# 4-digit-clock.net
KiCad netlist of a schematic drawn in EAGLE
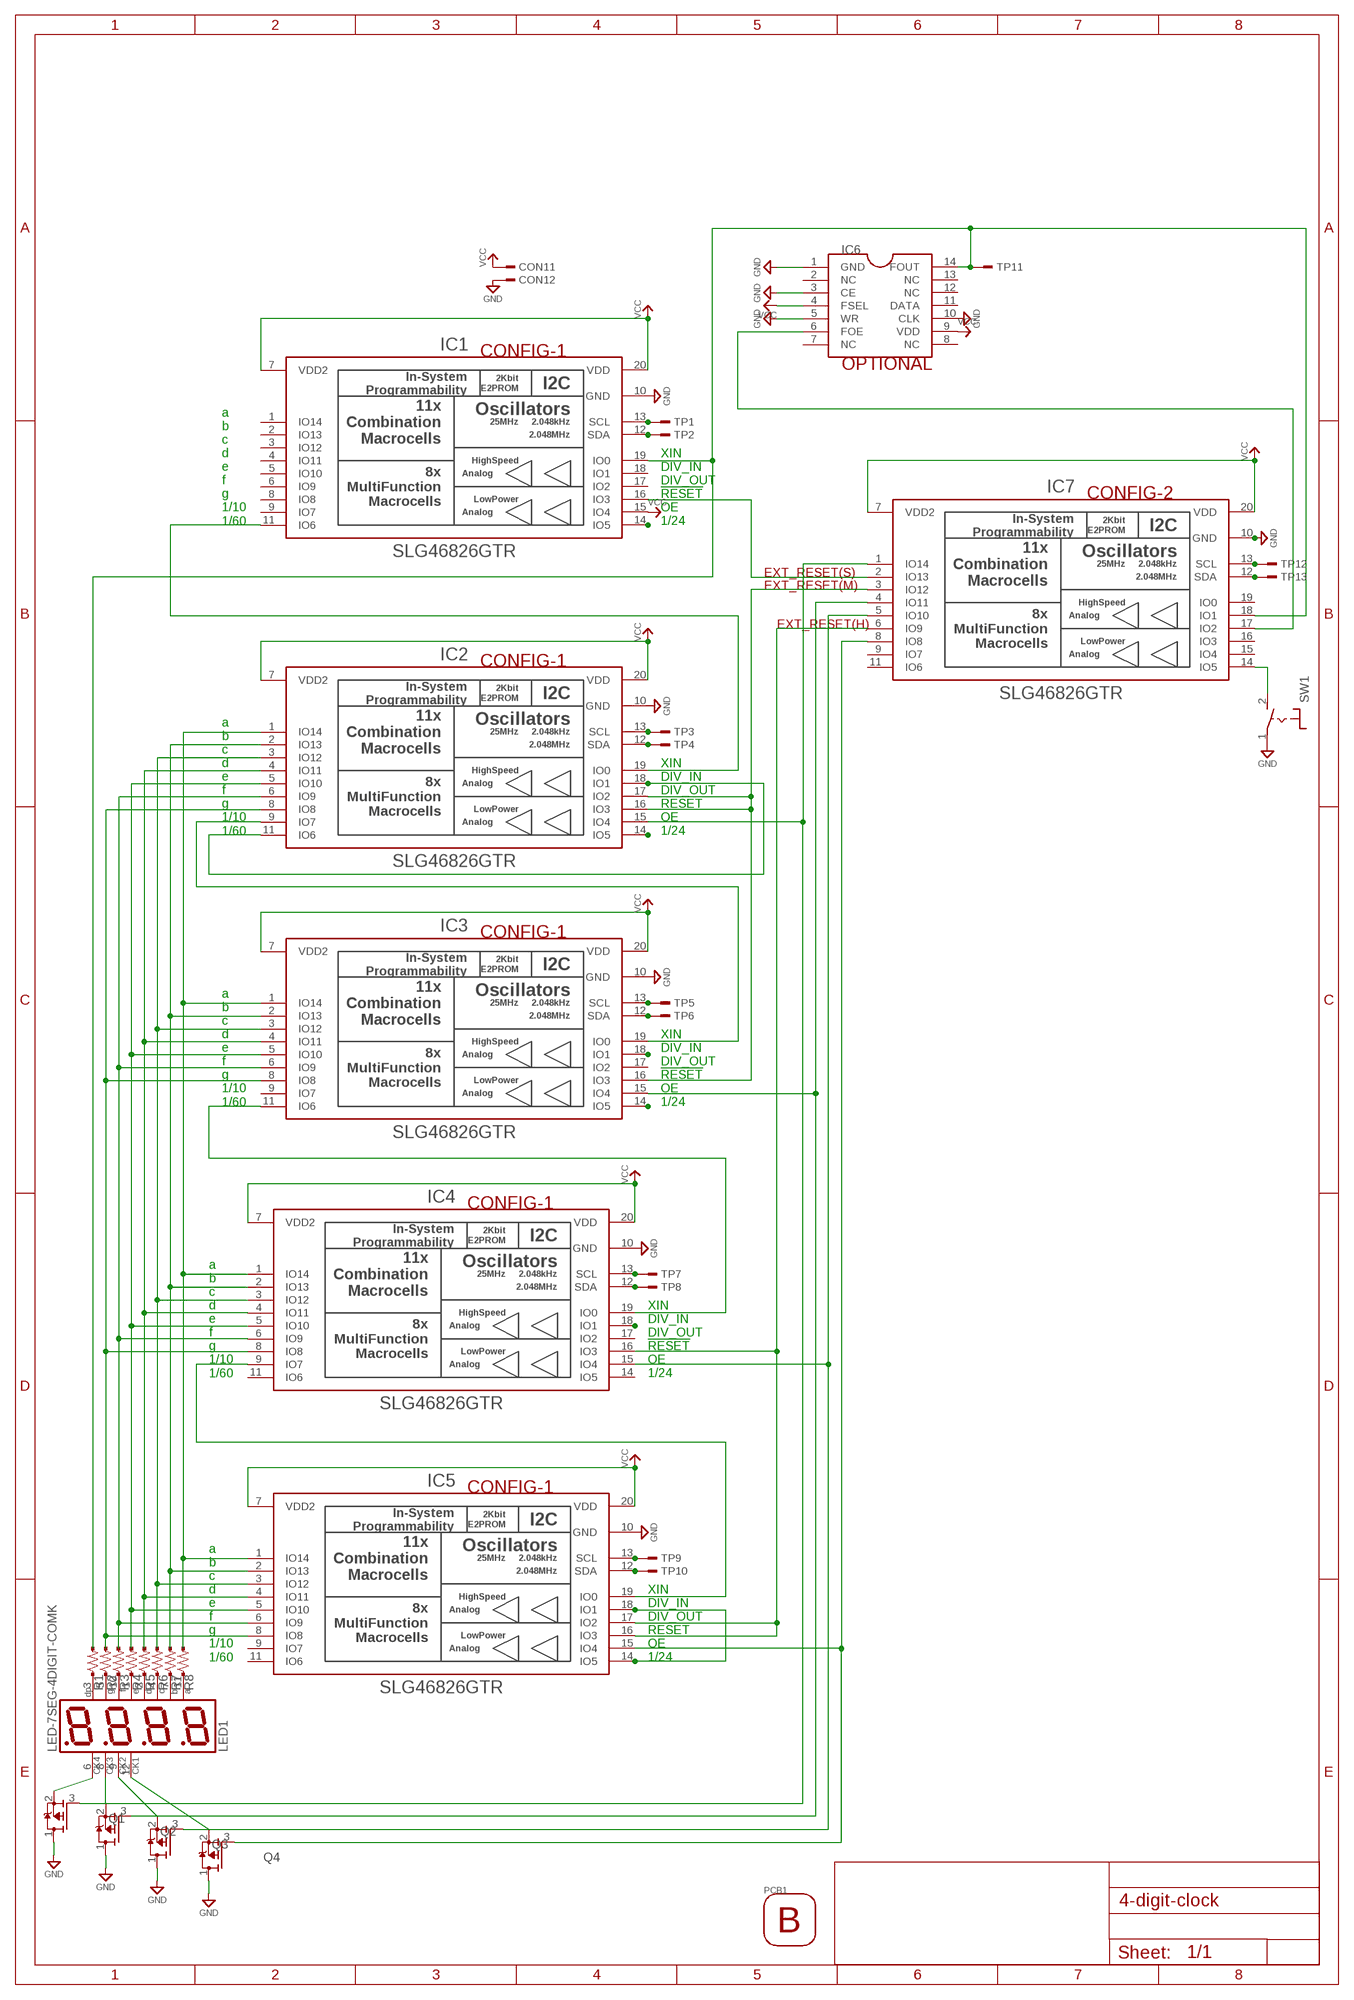
[diagram p0: schematic, sheet 1]

(export (version "E")
  (design (tool "Eeschema 10.0.6"))
  (components
    (comp (ref "CON1")
      (value "B2B-XH-A")
      (footprint "eagle-import:B2B-XH-A(LF)(SN)")
      (libsource (lib "eagle-import") (part "B2B-XH-A"))
    )
    (comp (ref "IC1")
      (value "SLG46826GTR")
      (footprint "eagle-import:SOT65P650X440-20N")
      (libsource (lib "eagle-import") (part "SLG46826GTR"))
    )
    (comp (ref "IC2")
      (value "SLG46826GTR")
      (footprint "eagle-import:SOT65P650X440-20N")
      (libsource (lib "eagle-import") (part "SLG46826GTR"))
    )
    (comp (ref "IC3")
      (value "SLG46826GTR")
      (footprint "eagle-import:SOT65P650X440-20N")
      (libsource (lib "eagle-import") (part "SLG46826GTR"))
    )
    (comp (ref "IC4")
      (value "SLG46826GTR")
      (footprint "eagle-import:SOT65P650X440-20N")
      (libsource (lib "eagle-import") (part "SLG46826GTR"))
    )
    (comp (ref "IC5")
      (value "SLG46826GTR")
      (footprint "eagle-import:SOT65P650X440-20N")
      (libsource (lib "eagle-import") (part "SLG46826GTR"))
    )
    (comp (ref "IC6")
      (value "RTC-4543SA")
      (footprint "eagle-import:SOT127P1010X500-14N")
      (libsource (lib "eagle-import") (part "RTC-4543SA"))
    )
    (comp (ref "IC7")
      (value "SLG46826GTR")
      (footprint "eagle-import:SOT65P650X440-20N")
      (libsource (lib "eagle-import") (part "SLG46826GTR"))
    )
    (comp (ref "LED1")
      (value "LED-7SEG-4DIGIT-COMK")
      (footprint "eagle-import:LED-7SEG-4DIGIT")
      (libsource (lib "eagle-import") (part "LED-7SEG-4DIGIT-COMK"))
    )
    (comp (ref "PCB1")
      (value "P-MCS78A")
      (footprint "eagle-import:P-MCS78A")
      (libsource (lib "eagle-import") (part "P-MCS78A"))
    )
    (comp (ref "Q1")
      (value "2N7002")
      (footprint "eagle-import:SOT95P300X140-3N")
      (libsource (lib "eagle-import") (part "2N7002"))
    )
    (comp (ref "Q2")
      (value "2N7002")
      (footprint "eagle-import:SOT95P300X140-3N")
      (libsource (lib "eagle-import") (part "2N7002"))
    )
    (comp (ref "Q3")
      (value "2N7002")
      (footprint "eagle-import:SOT95P300X140-3N")
      (libsource (lib "eagle-import") (part "2N7002"))
    )
    (comp (ref "Q4")
      (value "2N7002")
      (footprint "eagle-import:SOT95P300X140-3N")
      (libsource (lib "eagle-import") (part "2N7002"))
    )
    (comp (ref "R1")
      (value "R-US-1.0K-1005")
      (footprint "eagle-import:C0402")
      (libsource (lib "eagle-import") (part "R-US--10051.0K"))
    )
    (comp (ref "R2")
      (value "R-US-1.0K-1005")
      (footprint "eagle-import:C0402")
      (libsource (lib "eagle-import") (part "R-US--10051.0K"))
    )
    (comp (ref "R3")
      (value "R-US-1.0K-1005")
      (footprint "eagle-import:C0402")
      (libsource (lib "eagle-import") (part "R-US--10051.0K"))
    )
    (comp (ref "R4")
      (value "R-US-1.0K-1005")
      (footprint "eagle-import:C0402")
      (libsource (lib "eagle-import") (part "R-US--10051.0K"))
    )
    (comp (ref "R5")
      (value "R-US-1.0K-1005")
      (footprint "eagle-import:C0402")
      (libsource (lib "eagle-import") (part "R-US--10051.0K"))
    )
    (comp (ref "R6")
      (value "R-US-1.0K-1005")
      (footprint "eagle-import:C0402")
      (libsource (lib "eagle-import") (part "R-US--10051.0K"))
    )
    (comp (ref "R7")
      (value "R-US-1.0K-1005")
      (footprint "eagle-import:C0402")
      (libsource (lib "eagle-import") (part "R-US--10051.0K"))
    )
    (comp (ref "R8")
      (value "R-US-1.0K-1005")
      (footprint "eagle-import:C0402")
      (libsource (lib "eagle-import") (part "R-US--10051.0K"))
    )
    (comp (ref "SW1")
      (value "TACTSW2-BK-TL1105S")
      (footprint "eagle-import:SW-TACTSW-TL1105S")
      (libsource (lib "eagle-import") (part "TACTSW2--TL1105SBK"))
    )
    (comp (ref "TP1")
      (value "TESTPAD-1608")
      (footprint "eagle-import:TP-1608")
      (libsource (lib "eagle-import") (part "TESTPAD-1608"))
    )
    (comp (ref "TP2")
      (value "TESTPAD-1608")
      (footprint "eagle-import:TP-1608")
      (libsource (lib "eagle-import") (part "TESTPAD-1608"))
    )
    (comp (ref "TP3")
      (value "TESTPAD-1608")
      (footprint "eagle-import:TP-1608")
      (libsource (lib "eagle-import") (part "TESTPAD-1608"))
    )
    (comp (ref "TP4")
      (value "TESTPAD-1608")
      (footprint "eagle-import:TP-1608")
      (libsource (lib "eagle-import") (part "TESTPAD-1608"))
    )
    (comp (ref "TP5")
      (value "TESTPAD-1608")
      (footprint "eagle-import:TP-1608")
      (libsource (lib "eagle-import") (part "TESTPAD-1608"))
    )
    (comp (ref "TP6")
      (value "TESTPAD-1608")
      (footprint "eagle-import:TP-1608")
      (libsource (lib "eagle-import") (part "TESTPAD-1608"))
    )
    (comp (ref "TP7")
      (value "TESTPAD-1608")
      (footprint "eagle-import:TP-1608")
      (libsource (lib "eagle-import") (part "TESTPAD-1608"))
    )
    (comp (ref "TP8")
      (value "TESTPAD-1608")
      (footprint "eagle-import:TP-1608")
      (libsource (lib "eagle-import") (part "TESTPAD-1608"))
    )
    (comp (ref "TP9")
      (value "TESTPAD-1608")
      (footprint "eagle-import:TP-1608")
      (libsource (lib "eagle-import") (part "TESTPAD-1608"))
    )
    (comp (ref "TP10")
      (value "TESTPAD-1608")
      (footprint "eagle-import:TP-1608")
      (libsource (lib "eagle-import") (part "TESTPAD-1608"))
    )
    (comp (ref "TP11")
      (value "TESTPAD-1608")
      (footprint "eagle-import:TP-1608")
      (libsource (lib "eagle-import") (part "TESTPAD-1608"))
    )
    (comp (ref "TP12")
      (value "TESTPAD-1608")
      (footprint "eagle-import:TP-1608")
      (libsource (lib "eagle-import") (part "TESTPAD-1608"))
    )
    (comp (ref "TP13")
      (value "TESTPAD-1608")
      (footprint "eagle-import:TP-1608")
      (libsource (lib "eagle-import") (part "TESTPAD-1608"))
    )
  )
  (nets
    (net (code "1") (name "GND") (class "Default")
      (node (ref "CON1") (pin "2") (pinfunction "1_2") (pintype "passive"))
      (node (ref "IC1") (pin "10") (pinfunction "GND_10") (pintype "power_in"))
      (node (ref "IC2") (pin "10") (pinfunction "GND_10") (pintype "power_in"))
      (node (ref "IC3") (pin "10") (pinfunction "GND_10") (pintype "power_in"))
      (node (ref "IC4") (pin "10") (pinfunction "GND_10") (pintype "power_in"))
      (node (ref "IC5") (pin "10") (pinfunction "GND_10") (pintype "power_in"))
      (node (ref "IC6") (pin "1") (pinfunction "GND_1") (pintype "bidirectional"))
      (node (ref "IC6") (pin "10") (pinfunction "CLK_10") (pintype "bidirectional"))
      (node (ref "IC6") (pin "3") (pinfunction "CE_3") (pintype "bidirectional"))
      (node (ref "IC6") (pin "5") (pinfunction "WR_5") (pintype "bidirectional"))
      (node (ref "IC7") (pin "10") (pinfunction "GND_10") (pintype "power_in"))
      (node (ref "Q1") (pin "1") (pinfunction "D_1") (pintype "passive"))
      (node (ref "Q2") (pin "1") (pinfunction "D_1") (pintype "passive"))
      (node (ref "Q3") (pin "1") (pinfunction "D_1") (pintype "passive"))
      (node (ref "Q4") (pin "1") (pinfunction "D_1") (pintype "passive"))
      (node (ref "SW1") (pin "1") (pinfunction "P_1") (pintype "passive"))
    )
    (net (code "2") (name "Net-(IC1-IO0)") (class "Default")
      (node (ref "IC1") (pin "19") (pinfunction "IO0_19") (pintype "bidirectional"))
      (node (ref "IC6") (pin "14") (pinfunction "FOUT_14") (pintype "bidirectional"))
      (node (ref "IC7") (pin "18") (pinfunction "IO1_18") (pintype "bidirectional"))
      (node (ref "R1") (pin "2") (pinfunction "2_2") (pintype "passive"))
      (node (ref "TP11") (pin "TP") (pinfunction "1_TP") (pintype "passive"))
    )
    (net (code "3") (name "Net-(IC1-IO3)") (class "Default")
      (node (ref "IC1") (pin "16") (pinfunction "IO3_16") (pintype "bidirectional"))
      (node (ref "IC7") (pin "2") (pinfunction "IO13_2") (pintype "bidirectional"))
    )
    (net (code "4") (name "Net-(IC1-IO6)") (class "Default")
      (node (ref "IC1") (pin "11") (pinfunction "IO6_11") (pintype "bidirectional"))
      (node (ref "IC2") (pin "19") (pinfunction "IO0_19") (pintype "bidirectional"))
    )
    (net (code "5") (name "Net-(IC1-SCL)") (class "Default")
      (node (ref "IC1") (pin "13") (pinfunction "SCL_13") (pintype "bidirectional"))
      (node (ref "TP1") (pin "TP") (pinfunction "1_TP") (pintype "passive"))
    )
    (net (code "6") (name "Net-(IC1-SDA)") (class "Default")
      (node (ref "IC1") (pin "12") (pinfunction "SDA_12") (pintype "bidirectional"))
      (node (ref "TP2") (pin "TP") (pinfunction "1_TP") (pintype "passive"))
    )
    (net (code "7") (name "Net-(IC2-IO1)") (class "Default")
      (node (ref "IC2") (pin "11") (pinfunction "IO6_11") (pintype "bidirectional"))
      (node (ref "IC2") (pin "18") (pinfunction "IO1_18") (pintype "bidirectional"))
    )
    (net (code "8") (name "Net-(IC2-IO2)") (class "Default")
      (node (ref "IC2") (pin "16") (pinfunction "IO3_16") (pintype "bidirectional"))
      (node (ref "IC2") (pin "17") (pinfunction "IO2_17") (pintype "bidirectional"))
      (node (ref "IC3") (pin "16") (pinfunction "IO3_16") (pintype "bidirectional"))
      (node (ref "IC7") (pin "3") (pinfunction "IO12_3") (pintype "bidirectional"))
    )
    (net (code "9") (name "Net-(IC2-IO4)") (class "Default")
      (node (ref "IC2") (pin "15") (pinfunction "IO4_15") (pintype "bidirectional"))
      (node (ref "IC7") (pin "1") (pinfunction "IO14_1") (pintype "bidirectional"))
      (node (ref "Q1") (pin "3") (pinfunction "G_3") (pintype "passive"))
    )
    (net (code "10") (name "Net-(IC2-IO7)") (class "Default")
      (node (ref "IC2") (pin "9") (pinfunction "IO7_9") (pintype "bidirectional"))
      (node (ref "IC3") (pin "19") (pinfunction "IO0_19") (pintype "bidirectional"))
    )
    (net (code "11") (name "Net-(IC2-IO8)") (class "Default")
      (node (ref "IC2") (pin "8") (pinfunction "IO8_8") (pintype "bidirectional"))
      (node (ref "IC3") (pin "8") (pinfunction "IO8_8") (pintype "bidirectional"))
      (node (ref "IC4") (pin "8") (pinfunction "IO8_8") (pintype "bidirectional"))
      (node (ref "IC5") (pin "8") (pinfunction "IO8_8") (pintype "bidirectional"))
      (node (ref "R2") (pin "2") (pinfunction "2_2") (pintype "passive"))
    )
    (net (code "12") (name "Net-(IC2-IO9)") (class "Default")
      (node (ref "IC2") (pin "6") (pinfunction "IO9_6") (pintype "bidirectional"))
      (node (ref "IC3") (pin "6") (pinfunction "IO9_6") (pintype "bidirectional"))
      (node (ref "IC4") (pin "6") (pinfunction "IO9_6") (pintype "bidirectional"))
      (node (ref "IC5") (pin "6") (pinfunction "IO9_6") (pintype "bidirectional"))
      (node (ref "R3") (pin "2") (pinfunction "2_2") (pintype "passive"))
    )
    (net (code "13") (name "Net-(IC2-IO10)") (class "Default")
      (node (ref "IC2") (pin "5") (pinfunction "IO10_5") (pintype "bidirectional"))
      (node (ref "IC3") (pin "5") (pinfunction "IO10_5") (pintype "bidirectional"))
      (node (ref "IC4") (pin "5") (pinfunction "IO10_5") (pintype "bidirectional"))
      (node (ref "IC5") (pin "5") (pinfunction "IO10_5") (pintype "bidirectional"))
      (node (ref "R4") (pin "2") (pinfunction "2_2") (pintype "passive"))
    )
    (net (code "14") (name "Net-(IC2-IO11)") (class "Default")
      (node (ref "IC2") (pin "4") (pinfunction "IO11_4") (pintype "bidirectional"))
      (node (ref "IC3") (pin "4") (pinfunction "IO11_4") (pintype "bidirectional"))
      (node (ref "IC4") (pin "4") (pinfunction "IO11_4") (pintype "bidirectional"))
      (node (ref "IC5") (pin "4") (pinfunction "IO11_4") (pintype "bidirectional"))
      (node (ref "R5") (pin "2") (pinfunction "2_2") (pintype "passive"))
    )
    (net (code "15") (name "Net-(IC2-IO12)") (class "Default")
      (node (ref "IC2") (pin "3") (pinfunction "IO12_3") (pintype "bidirectional"))
      (node (ref "IC3") (pin "3") (pinfunction "IO12_3") (pintype "bidirectional"))
      (node (ref "IC4") (pin "3") (pinfunction "IO12_3") (pintype "bidirectional"))
      (node (ref "IC5") (pin "3") (pinfunction "IO12_3") (pintype "bidirectional"))
      (node (ref "R6") (pin "2") (pinfunction "2_2") (pintype "passive"))
    )
    (net (code "16") (name "Net-(IC2-IO13)") (class "Default")
      (node (ref "IC2") (pin "2") (pinfunction "IO13_2") (pintype "bidirectional"))
      (node (ref "IC3") (pin "2") (pinfunction "IO13_2") (pintype "bidirectional"))
      (node (ref "IC4") (pin "2") (pinfunction "IO13_2") (pintype "bidirectional"))
      (node (ref "IC5") (pin "2") (pinfunction "IO13_2") (pintype "bidirectional"))
      (node (ref "R7") (pin "2") (pinfunction "2_2") (pintype "passive"))
    )
    (net (code "17") (name "Net-(IC2-IO14)") (class "Default")
      (node (ref "IC2") (pin "1") (pinfunction "IO14_1") (pintype "bidirectional"))
      (node (ref "IC3") (pin "1") (pinfunction "IO14_1") (pintype "bidirectional"))
      (node (ref "IC4") (pin "1") (pinfunction "IO14_1") (pintype "bidirectional"))
      (node (ref "IC5") (pin "1") (pinfunction "IO14_1") (pintype "bidirectional"))
      (node (ref "R8") (pin "2") (pinfunction "2_2") (pintype "passive"))
    )
    (net (code "18") (name "Net-(IC2-SCL)") (class "Default")
      (node (ref "IC2") (pin "13") (pinfunction "SCL_13") (pintype "bidirectional"))
      (node (ref "TP3") (pin "TP") (pinfunction "1_TP") (pintype "passive"))
    )
    (net (code "19") (name "Net-(IC2-SDA)") (class "Default")
      (node (ref "IC2") (pin "12") (pinfunction "SDA_12") (pintype "bidirectional"))
      (node (ref "TP4") (pin "TP") (pinfunction "1_TP") (pintype "passive"))
    )
    (net (code "20") (name "Net-(IC3-IO4)") (class "Default")
      (node (ref "IC3") (pin "15") (pinfunction "IO4_15") (pintype "bidirectional"))
      (node (ref "IC7") (pin "4") (pinfunction "IO11_4") (pintype "bidirectional"))
      (node (ref "Q2") (pin "3") (pinfunction "G_3") (pintype "passive"))
    )
    (net (code "21") (name "Net-(IC3-IO6)") (class "Default")
      (node (ref "IC3") (pin "11") (pinfunction "IO6_11") (pintype "bidirectional"))
      (node (ref "IC4") (pin "19") (pinfunction "IO0_19") (pintype "bidirectional"))
    )
    (net (code "22") (name "Net-(IC3-SCL)") (class "Default")
      (node (ref "IC3") (pin "13") (pinfunction "SCL_13") (pintype "bidirectional"))
      (node (ref "TP5") (pin "TP") (pinfunction "1_TP") (pintype "passive"))
    )
    (net (code "23") (name "Net-(IC3-SDA)") (class "Default")
      (node (ref "IC3") (pin "12") (pinfunction "SDA_12") (pintype "bidirectional"))
      (node (ref "TP6") (pin "TP") (pinfunction "1_TP") (pintype "passive"))
    )
    (net (code "24") (name "Net-(IC4-IO3)") (class "Default")
      (node (ref "IC4") (pin "16") (pinfunction "IO3_16") (pintype "bidirectional"))
      (node (ref "IC5") (pin "16") (pinfunction "IO3_16") (pintype "bidirectional"))
      (node (ref "IC5") (pin "17") (pinfunction "IO2_17") (pintype "bidirectional"))
      (node (ref "IC7") (pin "6") (pinfunction "IO9_6") (pintype "bidirectional"))
    )
    (net (code "25") (name "Net-(IC4-IO4)") (class "Default")
      (node (ref "IC4") (pin "15") (pinfunction "IO4_15") (pintype "bidirectional"))
      (node (ref "IC7") (pin "5") (pinfunction "IO10_5") (pintype "bidirectional"))
      (node (ref "Q3") (pin "3") (pinfunction "G_3") (pintype "passive"))
    )
    (net (code "26") (name "Net-(IC4-IO7)") (class "Default")
      (node (ref "IC4") (pin "9") (pinfunction "IO7_9") (pintype "bidirectional"))
      (node (ref "IC5") (pin "19") (pinfunction "IO0_19") (pintype "bidirectional"))
    )
    (net (code "27") (name "Net-(IC4-SCL)") (class "Default")
      (node (ref "IC4") (pin "13") (pinfunction "SCL_13") (pintype "bidirectional"))
      (node (ref "TP7") (pin "TP") (pinfunction "1_TP") (pintype "passive"))
    )
    (net (code "28") (name "Net-(IC4-SDA)") (class "Default")
      (node (ref "IC4") (pin "12") (pinfunction "SDA_12") (pintype "bidirectional"))
      (node (ref "TP8") (pin "TP") (pinfunction "1_TP") (pintype "passive"))
    )
    (net (code "29") (name "Net-(IC5-IO1)") (class "Default")
      (node (ref "IC5") (pin "14") (pinfunction "IO5_14") (pintype "bidirectional"))
      (node (ref "IC5") (pin "18") (pinfunction "IO1_18") (pintype "bidirectional"))
    )
    (net (code "30") (name "Net-(IC5-IO4)") (class "Default")
      (node (ref "IC5") (pin "15") (pinfunction "IO4_15") (pintype "bidirectional"))
      (node (ref "IC7") (pin "8") (pinfunction "IO8_8") (pintype "bidirectional"))
      (node (ref "Q4") (pin "3") (pinfunction "G_3") (pintype "passive"))
    )
    (net (code "31") (name "Net-(IC5-SCL)") (class "Default")
      (node (ref "IC5") (pin "13") (pinfunction "SCL_13") (pintype "bidirectional"))
      (node (ref "TP9") (pin "TP") (pinfunction "1_TP") (pintype "passive"))
    )
    (net (code "32") (name "Net-(IC5-SDA)") (class "Default")
      (node (ref "IC5") (pin "12") (pinfunction "SDA_12") (pintype "bidirectional"))
      (node (ref "TP10") (pin "TP") (pinfunction "1_TP") (pintype "passive"))
    )
    (net (code "33") (name "Net-(IC6-FOE)") (class "Default")
      (node (ref "IC6") (pin "6") (pinfunction "FOE_6") (pintype "bidirectional"))
      (node (ref "IC7") (pin "17") (pinfunction "IO2_17") (pintype "bidirectional"))
    )
    (net (code "34") (name "Net-(IC7-IO5)") (class "Default")
      (node (ref "IC7") (pin "14") (pinfunction "IO5_14") (pintype "bidirectional"))
      (node (ref "SW1") (pin "2") (pinfunction "S_2") (pintype "passive"))
    )
    (net (code "35") (name "Net-(IC7-SCL)") (class "Default")
      (node (ref "IC7") (pin "13") (pinfunction "SCL_13") (pintype "bidirectional"))
      (node (ref "TP12") (pin "TP") (pinfunction "1_TP") (pintype "passive"))
    )
    (net (code "36") (name "Net-(IC7-SDA)") (class "Default")
      (node (ref "IC7") (pin "12") (pinfunction "SDA_12") (pintype "bidirectional"))
      (node (ref "TP13") (pin "TP") (pinfunction "1_TP") (pintype "passive"))
    )
    (net (code "37") (name "Net-(LED1-A)") (class "Default")
      (node (ref "LED1") (pin "11") (pinfunction "A_11") (pintype "passive"))
      (node (ref "R8") (pin "1") (pinfunction "1_1") (pintype "passive"))
    )
    (net (code "38") (name "Net-(LED1-B)") (class "Default")
      (node (ref "LED1") (pin "7") (pinfunction "B_7") (pintype "passive"))
      (node (ref "R7") (pin "1") (pinfunction "1_1") (pintype "passive"))
    )
    (net (code "39") (name "Net-(LED1-C)") (class "Default")
      (node (ref "LED1") (pin "4") (pinfunction "C_4") (pintype "passive"))
      (node (ref "R6") (pin "1") (pinfunction "1_1") (pintype "passive"))
    )
    (net (code "40") (name "Net-(LED1-CA4)") (class "Default")
      (node (ref "LED1") (pin "6") (pinfunction "CA4_6") (pintype "passive"))
      (node (ref "Q1") (pin "2") (pinfunction "S_2") (pintype "passive"))
    )
    (net (code "41") (name "Net-(LED1-D)") (class "Default")
      (node (ref "LED1") (pin "2") (pinfunction "D_2") (pintype "passive"))
      (node (ref "R5") (pin "1") (pinfunction "1_1") (pintype "passive"))
    )
    (net (code "42") (name "Net-(LED1-DP)") (class "Default")
      (node (ref "LED1") (pin "3") (pinfunction "DP_3") (pintype "passive"))
      (node (ref "R1") (pin "1") (pinfunction "1_1") (pintype "passive"))
    )
    (net (code "43") (name "Net-(LED1-E)") (class "Default")
      (node (ref "LED1") (pin "1") (pinfunction "E_1") (pintype "passive"))
      (node (ref "R4") (pin "1") (pinfunction "1_1") (pintype "passive"))
    )
    (net (code "44") (name "Net-(LED1-F)") (class "Default")
      (node (ref "LED1") (pin "10") (pinfunction "F_10") (pintype "passive"))
      (node (ref "R3") (pin "1") (pinfunction "1_1") (pintype "passive"))
    )
    (net (code "45") (name "Net-(LED1-G)") (class "Default")
      (node (ref "LED1") (pin "5") (pinfunction "G_5") (pintype "passive"))
      (node (ref "R2") (pin "1") (pinfunction "1_1") (pintype "passive"))
    )
    (net (code "46") (name "Net-(Q2-S)") (class "Default")
      (node (ref "LED1") (pin "8") (pinfunction "CA_8") (pintype "passive"))
      (node (ref "Q2") (pin "2") (pinfunction "S_2") (pintype "passive"))
    )
    (net (code "47") (name "Net-(Q3-S)") (class "Default")
      (node (ref "LED1") (pin "9") (pinfunction "CA_9") (pintype "passive"))
      (node (ref "Q3") (pin "2") (pinfunction "S_2") (pintype "passive"))
    )
    (net (code "48") (name "Net-(Q4-S)") (class "Default")
      (node (ref "LED1") (pin "12") (pinfunction "CA_12") (pintype "passive"))
      (node (ref "Q4") (pin "2") (pinfunction "S_2") (pintype "passive"))
    )
    (net (code "49") (name "VCC") (class "Default")
      (node (ref "CON1") (pin "1") (pinfunction "1_1") (pintype "passive"))
      (node (ref "IC1") (pin "15") (pinfunction "IO4_15") (pintype "bidirectional"))
      (node (ref "IC1") (pin "20") (pinfunction "VDD_20") (pintype "power_in"))
      (node (ref "IC1") (pin "7") (pinfunction "VDD2_7") (pintype "power_in"))
      (node (ref "IC2") (pin "20") (pinfunction "VDD_20") (pintype "power_in"))
      (node (ref "IC2") (pin "7") (pinfunction "VDD2_7") (pintype "power_in"))
      (node (ref "IC3") (pin "20") (pinfunction "VDD_20") (pintype "power_in"))
      (node (ref "IC3") (pin "7") (pinfunction "VDD2_7") (pintype "power_in"))
      (node (ref "IC4") (pin "20") (pinfunction "VDD_20") (pintype "power_in"))
      (node (ref "IC4") (pin "7") (pinfunction "VDD2_7") (pintype "power_in"))
      (node (ref "IC5") (pin "20") (pinfunction "VDD_20") (pintype "power_in"))
      (node (ref "IC5") (pin "7") (pinfunction "VDD2_7") (pintype "power_in"))
      (node (ref "IC6") (pin "4") (pinfunction "FSEL_4") (pintype "bidirectional"))
      (node (ref "IC6") (pin "9") (pinfunction "VDD_9") (pintype "bidirectional"))
      (node (ref "IC7") (pin "20") (pinfunction "VDD_20") (pintype "power_in"))
      (node (ref "IC7") (pin "7") (pinfunction "VDD2_7") (pintype "power_in"))
    )
    (net (code "50") (name "unconnected-(IC1-IO1-Pad18)") (class "Default")
      (node (ref "IC1") (pin "18") (pinfunction "IO1_18") (pintype "bidirectional"))
    )
    (net (code "51") (name "unconnected-(IC1-IO2-Pad17)") (class "Default")
      (node (ref "IC1") (pin "17") (pinfunction "IO2_17") (pintype "bidirectional"))
    )
    (net (code "52") (name "unconnected-(IC1-IO5-Pad14)") (class "Default")
      (node (ref "IC1") (pin "14") (pinfunction "IO5_14") (pintype "bidirectional"))
    )
    (net (code "53") (name "unconnected-(IC1-IO7-Pad9)") (class "Default")
      (node (ref "IC1") (pin "9") (pinfunction "IO7_9") (pintype "bidirectional"))
    )
    (net (code "54") (name "unconnected-(IC1-IO8-Pad8)") (class "Default")
      (node (ref "IC1") (pin "8") (pinfunction "IO8_8") (pintype "bidirectional"))
    )
    (net (code "55") (name "unconnected-(IC1-IO9-Pad6)") (class "Default")
      (node (ref "IC1") (pin "6") (pinfunction "IO9_6") (pintype "bidirectional"))
    )
    (net (code "56") (name "unconnected-(IC1-IO10-Pad5)") (class "Default")
      (node (ref "IC1") (pin "5") (pinfunction "IO10_5") (pintype "bidirectional"))
    )
    (net (code "57") (name "unconnected-(IC1-IO11-Pad4)") (class "Default")
      (node (ref "IC1") (pin "4") (pinfunction "IO11_4") (pintype "bidirectional"))
    )
    (net (code "58") (name "unconnected-(IC1-IO12-Pad3)") (class "Default")
      (node (ref "IC1") (pin "3") (pinfunction "IO12_3") (pintype "bidirectional"))
    )
    (net (code "59") (name "unconnected-(IC1-IO13-Pad2)") (class "Default")
      (node (ref "IC1") (pin "2") (pinfunction "IO13_2") (pintype "bidirectional"))
    )
    (net (code "60") (name "unconnected-(IC1-IO14-Pad1)") (class "Default")
      (node (ref "IC1") (pin "1") (pinfunction "IO14_1") (pintype "bidirectional"))
    )
    (net (code "61") (name "unconnected-(IC2-IO5-Pad14)") (class "Default")
      (node (ref "IC2") (pin "14") (pinfunction "IO5_14") (pintype "bidirectional"))
    )
    (net (code "62") (name "unconnected-(IC3-IO1-Pad18)") (class "Default")
      (node (ref "IC3") (pin "18") (pinfunction "IO1_18") (pintype "bidirectional"))
    )
    (net (code "63") (name "unconnected-(IC3-IO2-Pad17)") (class "Default")
      (node (ref "IC3") (pin "17") (pinfunction "IO2_17") (pintype "bidirectional"))
    )
    (net (code "64") (name "unconnected-(IC3-IO5-Pad14)") (class "Default")
      (node (ref "IC3") (pin "14") (pinfunction "IO5_14") (pintype "bidirectional"))
    )
    (net (code "65") (name "unconnected-(IC3-IO7-Pad9)") (class "Default")
      (node (ref "IC3") (pin "9") (pinfunction "IO7_9") (pintype "bidirectional"))
    )
    (net (code "66") (name "unconnected-(IC4-IO1-Pad18)") (class "Default")
      (node (ref "IC4") (pin "18") (pinfunction "IO1_18") (pintype "bidirectional"))
    )
    (net (code "67") (name "unconnected-(IC4-IO2-Pad17)") (class "Default")
      (node (ref "IC4") (pin "17") (pinfunction "IO2_17") (pintype "bidirectional"))
    )
    (net (code "68") (name "unconnected-(IC4-IO5-Pad14)") (class "Default")
      (node (ref "IC4") (pin "14") (pinfunction "IO5_14") (pintype "bidirectional"))
    )
    (net (code "69") (name "unconnected-(IC4-IO6-Pad11)") (class "Default")
      (node (ref "IC4") (pin "11") (pinfunction "IO6_11") (pintype "bidirectional"))
    )
    (net (code "70") (name "unconnected-(IC5-IO6-Pad11)") (class "Default")
      (node (ref "IC5") (pin "11") (pinfunction "IO6_11") (pintype "bidirectional"))
    )
    (net (code "71") (name "unconnected-(IC5-IO7-Pad9)") (class "Default")
      (node (ref "IC5") (pin "9") (pinfunction "IO7_9") (pintype "bidirectional"))
    )
    (net (code "72") (name "unconnected-(IC6-DATA-Pad11)") (class "Default")
      (node (ref "IC6") (pin "11") (pinfunction "DATA_11") (pintype "bidirectional"))
    )
    (net (code "73") (name "unconnected-(IC6-NC-Pad2)") (class "Default")
      (node (ref "IC6") (pin "2") (pinfunction "NC_2") (pintype "no_connect"))
    )
    (net (code "74") (name "unconnected-(IC6-NC-Pad7)") (class "Default")
      (node (ref "IC6") (pin "7") (pinfunction "NC_7") (pintype "no_connect"))
    )
    (net (code "75") (name "unconnected-(IC6-NC-Pad8)") (class "Default")
      (node (ref "IC6") (pin "8") (pinfunction "NC_8") (pintype "no_connect"))
    )
    (net (code "76") (name "unconnected-(IC6-NC-Pad12)") (class "Default")
      (node (ref "IC6") (pin "12") (pinfunction "NC_12") (pintype "no_connect"))
    )
    (net (code "77") (name "unconnected-(IC6-NC-Pad13)") (class "Default")
      (node (ref "IC6") (pin "13") (pinfunction "NC_13") (pintype "no_connect"))
    )
    (net (code "78") (name "unconnected-(IC7-IO0-Pad19)") (class "Default")
      (node (ref "IC7") (pin "19") (pinfunction "IO0_19") (pintype "bidirectional"))
    )
    (net (code "79") (name "unconnected-(IC7-IO3-Pad16)") (class "Default")
      (node (ref "IC7") (pin "16") (pinfunction "IO3_16") (pintype "bidirectional"))
    )
    (net (code "80") (name "unconnected-(IC7-IO4-Pad15)") (class "Default")
      (node (ref "IC7") (pin "15") (pinfunction "IO4_15") (pintype "bidirectional"))
    )
    (net (code "81") (name "unconnected-(IC7-IO6-Pad11)") (class "Default")
      (node (ref "IC7") (pin "11") (pinfunction "IO6_11") (pintype "bidirectional"))
    )
    (net (code "82") (name "unconnected-(IC7-IO7-Pad9)") (class "Default")
      (node (ref "IC7") (pin "9") (pinfunction "IO7_9") (pintype "bidirectional"))
    )
  )
)
